# MPPT.net
KiCad netlist of a schematic drawn in Altium Designer
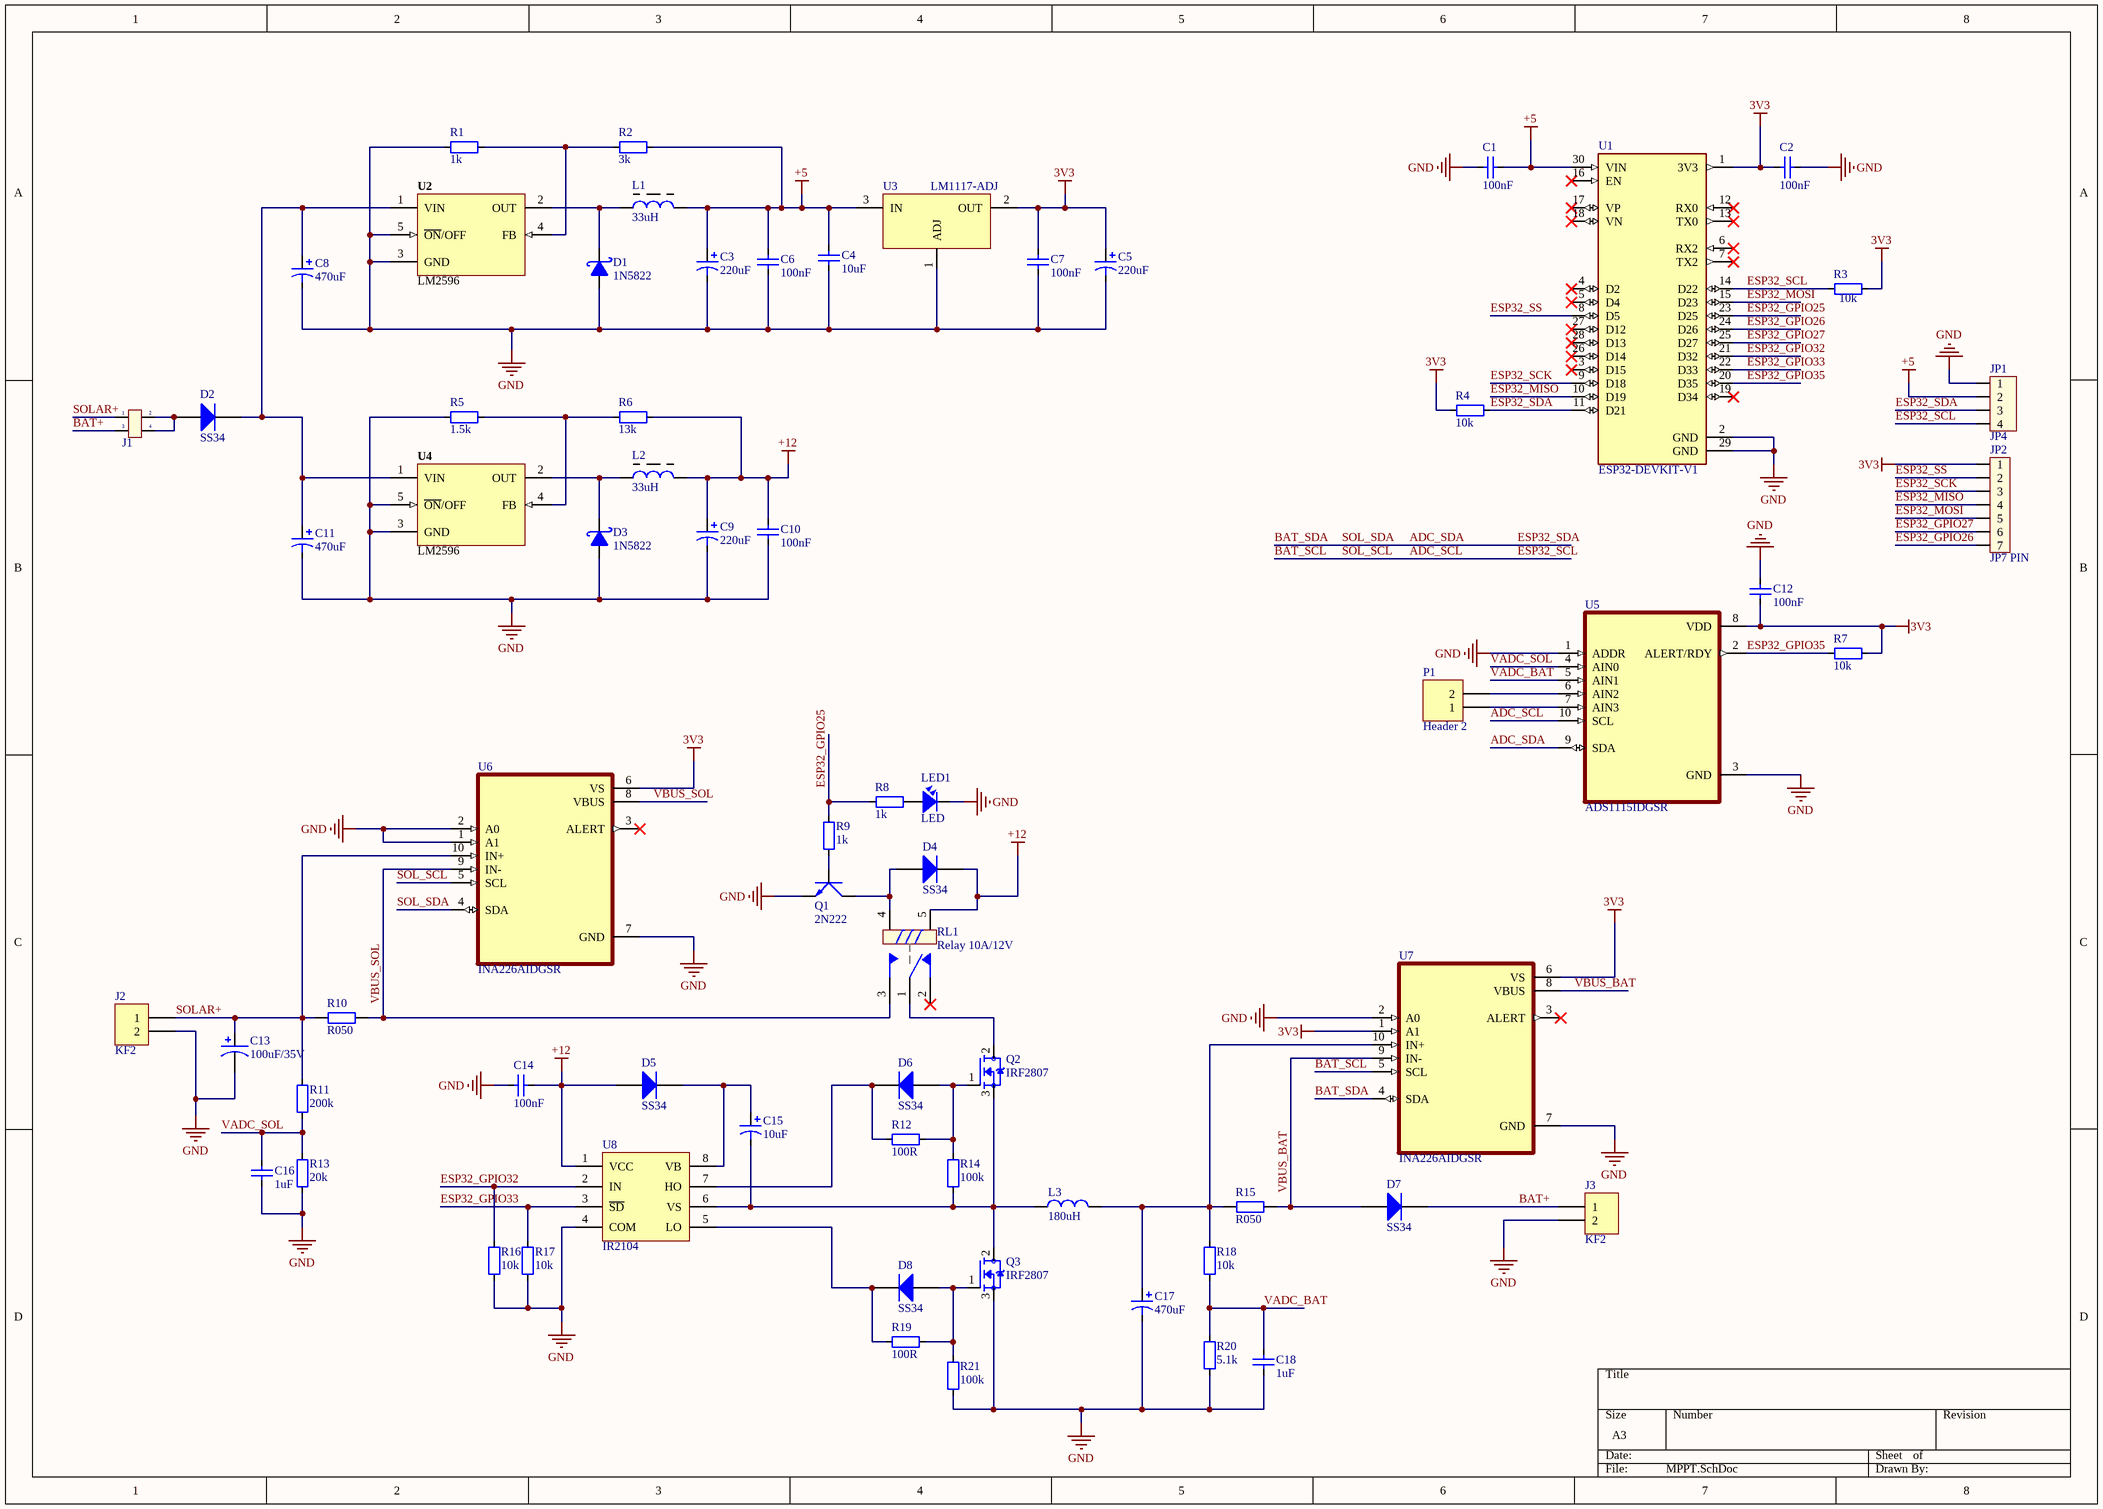
[diagram p0: MPPT.SchDoc]

(export (version "E")
  (design (tool "Eeschema 10.0.6"))
  (components
    (comp (ref "C1")
      (value "100nF")
      (footprint "CAP_0805")
      (description "Capacitor")
      (fields (field (name "PUBLISHER") "Altium Limited"))
      (libsource (lib "My Library") (part "CapSMD"))
    )
    (comp (ref "C2")
      (value "100nF")
      (footprint "CAP_0805")
      (description "Capacitor")
      (fields (field (name "PUBLISHER") "Altium Limited"))
      (libsource (lib "My Library") (part "CapSMD"))
    )
    (comp (ref "C3")
      (value "220uF")
      (footprint "C8mm")
      (description "220uF 25V 6x7mm")
      (fields (field (name "PUBLISHER") "Altium Limited"))
      (libsource (lib "My Library") (part "Cap Pol"))
    )
    (comp (ref "C4")
      (value "10uF")
      (footprint "CAP_0805")
      (description "Capacitor")
      (fields (field (name "PUBLISHER") "Altium Limited"))
      (libsource (lib "My Library") (part "CapSMD"))
    )
    (comp (ref "C5")
      (value "220uF")
      (footprint "C8mm")
      (description "220uF 25V 6x7mm")
      (fields (field (name "PUBLISHER") "Altium Limited"))
      (libsource (lib "My Library") (part "Cap Pol"))
    )
    (comp (ref "C6")
      (value "100nF")
      (footprint "CAP_0805")
      (description "Capacitor")
      (fields (field (name "PUBLISHER") "Altium Limited"))
      (libsource (lib "My Library") (part "CapSMD"))
    )
    (comp (ref "C7")
      (value "100nF")
      (footprint "CAP_0805")
      (description "Capacitor")
      (fields (field (name "PUBLISHER") "Altium Limited"))
      (libsource (lib "My Library") (part "CapSMD"))
    )
    (comp (ref "C8")
      (value "470uF")
      (footprint "C8mm")
      (description "220uF 50V 8x12mm")
      (fields (field (name "PUBLISHER") "Altium Limited"))
      (libsource (lib "My Library") (part "Cap Pol"))
    )
    (comp (ref "C9")
      (value "220uF")
      (footprint "C8mm")
      (description "220uF 25V 6x7mm")
      (fields (field (name "PUBLISHER") "Altium Limited"))
      (libsource (lib "My Library") (part "Cap Pol"))
    )
    (comp (ref "C10")
      (value "100nF")
      (footprint "CAP_0805")
      (description "Capacitor")
      (fields (field (name "PUBLISHER") "Altium Limited"))
      (libsource (lib "My Library") (part "CapSMD"))
    )
    (comp (ref "C11")
      (value "470uF")
      (footprint "C8mm")
      (description "220uF 50V 8x12mm")
      (fields (field (name "PUBLISHER") "Altium Limited"))
      (libsource (lib "My Library") (part "Cap Pol"))
    )
    (comp (ref "C12")
      (value "100nF")
      (footprint "CAP_0805")
      (description "Capacitor")
      (fields (field (name "PUBLISHER") "Altium Limited"))
      (libsource (lib "My Library") (part "CapSMD"))
    )
    (comp (ref "C13")
      (value "100uF/35V")
      (footprint "CA-ALU-6.3")
      (description "Polarized Capacitor (Axial)")
      (fields (field (name "PUBLISHER") "Altium Limited"))
      (libsource (lib "") (part "Cap Pol_1"))
    )
    (comp (ref "C14")
      (value "100nF")
      (footprint "CAP_0805")
      (description "Capacitor")
      (fields (field (name "PUBLISHER") "Altium Limited"))
      (libsource (lib "My Library") (part "CapSMD"))
    )
    (comp (ref "C15")
      (value "10uF")
      (footprint "CAP_35TQC10MYF")
      (description "220uF 25V 6x7mm")
      (fields (field (name "PUBLISHER") "Altium Limited"))
      (libsource (lib "My Library") (part "Cap Pol"))
    )
    (comp (ref "C16")
      (value "1uF")
      (footprint "CAP_0805")
      (description "Capacitor")
      (fields (field (name "PUBLISHER") "Altium Limited"))
      (libsource (lib "My Library") (part "CapSMD"))
    )
    (comp (ref "C17")
      (value "470uF")
      (footprint "C8mm")
      (description "470uF 50V 8x12mm")
      (fields (field (name "PUBLISHER") "Altium Limited"))
      (libsource (lib "My Library") (part "Cap Pol"))
    )
    (comp (ref "C18")
      (value "1uF")
      (footprint "CAP_0805")
      (description "Capacitor")
      (fields (field (name "PUBLISHER") "Altium Limited"))
      (libsource (lib "My Library") (part "CapSMD"))
    )
    (comp (ref "D1")
      (value "1N5822")
      (footprint "SMA")
      (description "Schottky Rectifiers")
      (libsource (lib "My Library") (part "1N5822"))
    )
    (comp (ref "D2")
      (value "SS34")
      (footprint "SMA")
      (description "Dán")
      (libsource (lib "Altium_Lib_by_KhueNguyenCreator") (part "Diode SS34 ( 1N5822 )"))
    )
    (comp (ref "D3")
      (value "1N5822")
      (footprint "SMA")
      (description "Schottky Rectifiers")
      (libsource (lib "My Library") (part "1N5822"))
    )
    (comp (ref "D4")
      (value "SS34")
      (footprint "SMA")
      (libsource (lib "Altium_Lib_by_KhueNguyenCreator") (part "Diode SS34 ( 1N5822 )"))
    )
    (comp (ref "D5")
      (value "SS34")
      (footprint "SMA")
      (libsource (lib "Altium_Lib_by_KhueNguyenCreator") (part "Diode SS34 ( 1N5822 )"))
    )
    (comp (ref "D6")
      (value "SS34")
      (footprint "SMA")
      (description "Dán")
      (libsource (lib "Altium_Lib_by_KhueNguyenCreator") (part "Diode SS34 ( 1N5822 )"))
    )
    (comp (ref "D7")
      (value "SS34")
      (footprint "SMA")
      (description "Dán")
      (libsource (lib "Altium_Lib_by_KhueNguyenCreator") (part "Diode SS34 ( 1N5822 )"))
    )
    (comp (ref "D8")
      (value "SS34")
      (footprint "SMA")
      (description "Dán")
      (libsource (lib "Altium_Lib_by_KhueNguyenCreator") (part "Diode SS34 ( 1N5822 )"))
    )
    (comp (ref "J1") (value "Jumper 2x2") (footprint "HDR2X2") (libsource (lib "My Library") (part "JP2x2")))
    (comp (ref "J2")
      (value "KF2")
      (footprint "KF2-5.08T")
      (fields
        (field (name "MANUFACTURER") "Würth Elektronik eiSos GmbH")
        (field (name "PARTNO") "691103110002")
        (field (name "CREATED BY") "Karrer Zheng")
      )
      (libsource (lib "") (part "KF2_1"))
    )
    (comp (ref "J3")
      (value "KF2")
      (footprint "KF2-5.08T")
      (fields
        (field (name "MANUFACTURER") "Würth Elektronik eiSos GmbH")
        (field (name "PARTNO") "691103110002")
        (field (name "CREATED BY") "Karrer Zheng")
      )
      (libsource (lib "My Library") (part "KF2"))
    )
    (comp (ref "JP1")
      (value "JP4")
      (footprint "CON4")
      (description "Connector 4")
      (libsource (lib "My Library") (part "Con4"))
    )
    (comp (ref "JP2") (value "JP7 PIN") (footprint "JP7") (libsource (lib "My Library") (part "JP7")))
    (comp (ref "L1")
      (value "33uH")
      (footprint "L-SMD-M-7.3x4.5")
      (description "33uH CD127 3A 12x12x7mm")
      (libsource (lib "My Library") (part "Inductor Ferit"))
    )
    (comp (ref "L2")
      (value "33uH")
      (footprint "L-SMD-M-7.3x4.5")
      (description "33uH CD127 3A 12x12x7mm")
      (libsource (lib "My Library") (part "Inductor Ferit"))
    )
    (comp (ref "L3")
      (value "180uH")
      (footprint "L-DIP-M-13.5x6")
      (description "180uH 4A 13mm")
      (libsource (lib "My Library") (part "Inductor"))
    )
    (comp (ref "LED1")
      (value "LED")
      (footprint "LED-0805-Red")
      (description "LED Single colour Green and Red")
      (libsource (lib "My Library") (part "LED"))
    )
    (comp (ref "P1")
      (value "Header 2")
      (footprint "HDR1X2")
      (description "Header, 2-Pin")
      (fields (field (name "PUBLISHER") "Altium Limited"))
      (libsource (lib "My Library") (part "Header 2"))
    )
    (comp (ref "Q1")
      (value "2N222")
      (footprint "SOT23")
      (description "NPN 600mW, ECB")
      (libsource (lib "My Library") (part "2N222"))
    )
    (comp (ref "Q2") (value "IRF2807") (footprint "TO-220") (libsource (lib "My Library") (part "IRF2807")))
    (comp (ref "Q3") (value "IRF2807") (footprint "TO-220") (libsource (lib "My Library") (part "IRF2807")))
    (comp (ref "R1")
      (value "1k")
      (footprint "RES-SMD-0805")
      (description "Resistor")
      (fields
        (field (name "MANUFACTURER") "Generic Components")
        (field (name "PUBLISHER") "Altium Hobart Technology Centre")
      )
      (libsource (lib "My Library") (part "Resistor - SMD"))
    )
    (comp (ref "R2")
      (value "3k")
      (footprint "RES-SMD-0805")
      (description "Resistor")
      (fields
        (field (name "MANUFACTURER") "Generic Components")
        (field (name "PUBLISHER") "Altium Hobart Technology Centre")
      )
      (libsource (lib "My Library") (part "Resistor - SMD"))
    )
    (comp (ref "R3")
      (value "10k")
      (footprint "RES-SMD-0805")
      (description "Resistor")
      (fields
        (field (name "MANUFACTURER") "Generic Components")
        (field (name "PUBLISHER") "Altium Hobart Technology Centre")
      )
      (libsource (lib "My Library") (part "Resistor - SMD"))
    )
    (comp (ref "R4")
      (value "10k")
      (footprint "RES-SMD-0805")
      (description "Resistor")
      (fields
        (field (name "MANUFACTURER") "Generic Components")
        (field (name "PUBLISHER") "Altium Hobart Technology Centre")
      )
      (libsource (lib "My Library") (part "Resistor - SMD"))
    )
    (comp (ref "R5")
      (value "1.5k")
      (footprint "RES-SMD-0805")
      (description "Resistor")
      (fields
        (field (name "MANUFACTURER") "Generic Components")
        (field (name "PUBLISHER") "Altium Hobart Technology Centre")
      )
      (libsource (lib "My Library") (part "Resistor - SMD"))
    )
    (comp (ref "R6")
      (value "13k")
      (footprint "RES-SMD-0805")
      (description "Resistor")
      (fields
        (field (name "MANUFACTURER") "Generic Components")
        (field (name "PUBLISHER") "Altium Hobart Technology Centre")
      )
      (libsource (lib "My Library") (part "Resistor - SMD"))
    )
    (comp (ref "R7")
      (value "10k")
      (footprint "RES-SMD-0805")
      (description "Resistor")
      (fields
        (field (name "MANUFACTURER") "Generic Components")
        (field (name "PUBLISHER") "Altium Hobart Technology Centre")
      )
      (libsource (lib "My Library") (part "Resistor - SMD"))
    )
    (comp (ref "R8")
      (value "1k")
      (footprint "RES-SMD-0805")
      (description "Resistor")
      (fields
        (field (name "MANUFACTURER") "Generic Components")
        (field (name "PUBLISHER") "Altium Hobart Technology Centre")
      )
      (libsource (lib "My Library") (part "Resistor - SMD"))
    )
    (comp (ref "R9")
      (value "1k")
      (footprint "RES-SMD-0805")
      (description "Resistor")
      (fields
        (field (name "MANUFACTURER") "Generic Components")
        (field (name "PUBLISHER") "Altium Hobart Technology Centre")
      )
      (libsource (lib "My Library") (part "Resistor - SMD"))
    )
    (comp (ref "R10")
      (value "R050")
      (footprint "RES-SMD-2512")
      (description "Resistor SMD")
      (fields
        (field (name "MANUFACTURER") "Generic Components")
        (field (name "PUBLISHER") "Altium Hobart Technology Centre")
      )
      (libsource (lib "") (part "Resistor - SMD_1"))
    )
    (comp (ref "R11")
      (value "200k")
      (footprint "RES-SMD-0805")
      (description "Resistor")
      (fields
        (field (name "MANUFACTURER") "Generic Components")
        (field (name "PUBLISHER") "Altium Hobart Technology Centre")
      )
      (libsource (lib "My Library") (part "Resistor - SMD"))
    )
    (comp (ref "R12")
      (value "100R")
      (footprint "RES-SMD-0805")
      (description "Resistor")
      (fields
        (field (name "MANUFACTURER") "Generic Components")
        (field (name "PUBLISHER") "Altium Hobart Technology Centre")
      )
      (libsource (lib "My Library") (part "Resistor - SMD"))
    )
    (comp (ref "R13")
      (value "20k")
      (footprint "RES-SMD-0805")
      (description "Resistor")
      (fields
        (field (name "MANUFACTURER") "Generic Components")
        (field (name "PUBLISHER") "Altium Hobart Technology Centre")
      )
      (libsource (lib "My Library") (part "Resistor - SMD"))
    )
    (comp (ref "R14")
      (value "100k")
      (footprint "RES-SMD-0805")
      (description "Resistor")
      (fields
        (field (name "MANUFACTURER") "Generic Components")
        (field (name "PUBLISHER") "Altium Hobart Technology Centre")
      )
      (libsource (lib "My Library") (part "Resistor - SMD"))
    )
    (comp (ref "R15")
      (value "R050")
      (footprint "RES-SMD-2512")
      (description "Resistor SMD")
      (fields
        (field (name "MANUFACTURER") "Generic Components")
        (field (name "PUBLISHER") "Altium Hobart Technology Centre")
      )
      (libsource (lib "") (part "Resistor - SMD_1"))
    )
    (comp (ref "R16")
      (value "10k")
      (footprint "RES-SMD-0805")
      (description "Resistor")
      (fields
        (field (name "MANUFACTURER") "Generic Components")
        (field (name "PUBLISHER") "Altium Hobart Technology Centre")
      )
      (libsource (lib "My Library") (part "Resistor - SMD"))
    )
    (comp (ref "R17")
      (value "10k")
      (footprint "RES-SMD-0805")
      (description "Resistor")
      (fields
        (field (name "MANUFACTURER") "Generic Components")
        (field (name "PUBLISHER") "Altium Hobart Technology Centre")
      )
      (libsource (lib "My Library") (part "Resistor - SMD"))
    )
    (comp (ref "R18")
      (value "10k")
      (footprint "RES-SMD-0805")
      (description "Resistor")
      (fields
        (field (name "MANUFACTURER") "Generic Components")
        (field (name "PUBLISHER") "Altium Hobart Technology Centre")
      )
      (libsource (lib "My Library") (part "Resistor - SMD"))
    )
    (comp (ref "R19")
      (value "100R")
      (footprint "RES-SMD-0805")
      (description "Resistor")
      (fields
        (field (name "MANUFACTURER") "Generic Components")
        (field (name "PUBLISHER") "Altium Hobart Technology Centre")
      )
      (libsource (lib "My Library") (part "Resistor - SMD"))
    )
    (comp (ref "R20")
      (value "5.1k")
      (footprint "RES-SMD-0805")
      (description "Resistor")
      (fields
        (field (name "MANUFACTURER") "Generic Components")
        (field (name "PUBLISHER") "Altium Hobart Technology Centre")
      )
      (libsource (lib "My Library") (part "Resistor - SMD"))
    )
    (comp (ref "R21")
      (value "100k")
      (footprint "RES-SMD-0805")
      (description "Resistor")
      (fields
        (field (name "MANUFACTURER") "Generic Components")
        (field (name "PUBLISHER") "Altium Hobart Technology Centre")
      )
      (libsource (lib "My Library") (part "Resistor - SMD"))
    )
    (comp (ref "RL1")
      (value "Relay 10A/12V")
      (footprint "RELAY5PIN-10A")
      (description "Relay SPDT,10A - 12VDC 5 Pin")
      (libsource (lib "My Library") (part "Relay 5"))
    )
    (comp (ref "U1")
      (value "ESP32-DEVKIT-V1")
      (footprint "MODULE_ESP32_DEVKIT_V1")
      (libsource (lib "ESP32-DEVKIT-V1") (part "ESP32-DEVKIT-V1"))
    )
    (comp (ref "U2") (value "LM2596") (footprint "TO-263") (libsource (lib "My Library") (part "LM2596")))
    (comp (ref "U3")
      (value "LM1117-ADJ")
      (footprint "LM1117-SOP")
      (description "800mA Low-Dropout Linear Regulator")
      (fields (field (name "CREATOR") "Nguyen Ba Bien"))
      (libsource (lib "My Library") (part "LM1117-ADJ"))
    )
    (comp (ref "U4") (value "LM2596") (footprint "TO-263") (libsource (lib "My Library") (part "LM2596")))
    (comp (ref "U5")
      (value "ADS1115IDGSR")
      (footprint "SOP50P490X110-10N")
      (libsource (lib "ADS1115IDGSR") (part "ADS1115IDGSR"))
    )
    (comp (ref "U6")
      (value "INA226AIDGSR")
      (footprint "SOP50P490X110-10N")
      (description "36V, 16-bit, ultra-precise i2c output current/voltage/power monitor w/alert 10-VSSOP -40 to 125")
      (fields
        (field (name "MF") "Texas Instruments")
        (field (name "BUYPART") "https://www.snapeda.com/parts/INA226AIDGSR/Texas%20Instruments/view-part/53552/?ref=eda")
      )
      (libsource (lib "INA226AIDGSR") (part "INA226AIDGSR"))
    )
    (comp (ref "U7")
      (value "INA226AIDGSR")
      (footprint "SOP50P490X110-10N")
      (description "36V, 16-bit, ultra-precise i2c output current/voltage/power monitor w/alert 10-VSSOP -40 to 125")
      (fields
        (field (name "MF") "Texas Instruments")
        (field (name "BUYPART") "https://www.snapeda.com/parts/INA226AIDGSR/Texas%20Instruments/view-part/53552/?ref=eda")
      )
      (libsource (lib "INA226AIDGSR") (part "INA226AIDGSR"))
    )
    (comp (ref "U8")
      (value "IR2104")
      (footprint "SO-8N")
      (description "Half-Bridge Driver")
      (libsource (lib "My Library") (part "IR2184"))
    )
  )
  (nets
    (net (code "1") (name "+5") (class "Default")
      (node (ref "C1") (pin "2") (pinfunction "2_2") (pintype "passive"))
      (node (ref "C3") (pin "1") (pinfunction "1_1") (pintype "passive"))
      (node (ref "C4") (pin "1") (pinfunction "1_1") (pintype "passive"))
      (node (ref "C6") (pin "1") (pinfunction "1_1") (pintype "passive"))
      (node (ref "JP1") (pin "2") (pinfunction "2_2") (pintype "passive"))
      (node (ref "L1") (pin "2") (pinfunction "2_2") (pintype "passive"))
      (node (ref "R2") (pin "2") (pinfunction "2_2") (pintype "passive"))
      (node (ref "U1") (pin "30") (pinfunction "VIN_30") (pintype "input"))
      (node (ref "U3") (pin "3") (pinfunction "IN_3") (pintype "passive"))
    )
    (net (code "2") (name "+12") (class "Default")
      (node (ref "C10") (pin "1") (pinfunction "1_1") (pintype "passive"))
      (node (ref "C14") (pin "1") (pinfunction "1_1") (pintype "passive"))
      (node (ref "C9") (pin "1") (pinfunction "1_1") (pintype "passive"))
      (node (ref "D4") (pin "2") (pinfunction "K_2") (pintype "passive"))
      (node (ref "D5") (pin "1") (pinfunction "A_1") (pintype "passive"))
      (node (ref "L2") (pin "2") (pinfunction "2_2") (pintype "passive"))
      (node (ref "R6") (pin "2") (pinfunction "2_2") (pintype "passive"))
      (node (ref "RL1") (pin "5") (pinfunction "5_5") (pintype "passive"))
      (node (ref "U8") (pin "1") (pinfunction "VCC_1") (pintype "passive"))
    )
    (net (code "3") (name "/ADC_SCL") (class "Default")
      (node (ref "JP1") (pin "4") (pinfunction "4_4") (pintype "passive"))
      (node (ref "R3") (pin "2") (pinfunction "2_2") (pintype "passive"))
      (node (ref "U1") (pin "14") (pinfunction "D22_14") (pintype "bidirectional"))
      (node (ref "U5") (pin "10") (pinfunction "SCL_10") (pintype "input"))
      (node (ref "U6") (pin "5") (pinfunction "SCL_5") (pintype "input"))
      (node (ref "U7") (pin "5") (pinfunction "SCL_5") (pintype "input"))
    )
    (net (code "4") (name "/ADC_SDA") (class "Default")
      (node (ref "JP1") (pin "3") (pinfunction "3_3") (pintype "passive"))
      (node (ref "R4") (pin "2") (pinfunction "2_2") (pintype "passive"))
      (node (ref "U1") (pin "11") (pinfunction "D21_11") (pintype "bidirectional"))
      (node (ref "U5") (pin "9") (pinfunction "SDA_9") (pintype "bidirectional"))
      (node (ref "U6") (pin "4") (pinfunction "SDA_4") (pintype "bidirectional"))
      (node (ref "U7") (pin "4") (pinfunction "SDA_4") (pintype "bidirectional"))
    )
    (net (code "5") (name "/BAT+") (class "Default")
      (node (ref "D7") (pin "2") (pinfunction "K_2") (pintype "passive"))
      (node (ref "J1") (pin "3") (pinfunction "3_3") (pintype "passive"))
      (node (ref "J3") (pin "1") (pinfunction "1_1") (pintype "passive"))
    )
    (net (code "6") (name "/ESP32_GPIO25") (class "Default")
      (node (ref "R8") (pin "2") (pinfunction "2_2") (pintype "passive"))
      (node (ref "R9") (pin "2") (pinfunction "2_2") (pintype "passive"))
      (node (ref "U1") (pin "23") (pinfunction "D25_23") (pintype "bidirectional"))
    )
    (net (code "7") (name "/ESP32_GPIO26") (class "Default")
      (node (ref "JP2") (pin "7") (pinfunction "7_7") (pintype "passive"))
      (node (ref "U1") (pin "24") (pinfunction "D26_24") (pintype "bidirectional"))
    )
    (net (code "8") (name "/ESP32_GPIO27") (class "Default")
      (node (ref "JP2") (pin "6") (pinfunction "6_6") (pintype "passive"))
      (node (ref "U1") (pin "25") (pinfunction "D27_25") (pintype "bidirectional"))
    )
    (net (code "9") (name "/ESP32_GPIO32") (class "Default")
      (node (ref "R16") (pin "2") (pinfunction "2_2") (pintype "passive"))
      (node (ref "U1") (pin "21") (pinfunction "D32_21") (pintype "bidirectional"))
      (node (ref "U8") (pin "2") (pinfunction "IN_2") (pintype "passive"))
    )
    (net (code "10") (name "/ESP32_GPIO33") (class "Default")
      (node (ref "R17") (pin "2") (pinfunction "2_2") (pintype "passive"))
      (node (ref "U1") (pin "22") (pinfunction "D33_22") (pintype "bidirectional"))
      (node (ref "U8") (pin "3") (pinfunction "~{SD}_3") (pintype "passive"))
    )
    (net (code "11") (name "/ESP32_GPIO35") (class "Default")
      (node (ref "R7") (pin "2") (pinfunction "2_2") (pintype "passive"))
      (node (ref "U1") (pin "20") (pinfunction "D35_20") (pintype "bidirectional"))
      (node (ref "U5") (pin "2") (pinfunction "ALERT/RDY_2") (pintype "output"))
    )
    (net (code "12") (name "/ESP32_MISO") (class "Default")
      (node (ref "JP2") (pin "4") (pinfunction "4_4") (pintype "passive"))
      (node (ref "U1") (pin "10") (pinfunction "D19_10") (pintype "bidirectional"))
    )
    (net (code "13") (name "/ESP32_MOSI") (class "Default")
      (node (ref "JP2") (pin "5") (pinfunction "5_5") (pintype "passive"))
      (node (ref "U1") (pin "15") (pinfunction "D23_15") (pintype "bidirectional"))
    )
    (net (code "14") (name "/ESP32_SCK") (class "Default")
      (node (ref "JP2") (pin "3") (pinfunction "3_3") (pintype "passive"))
      (node (ref "U1") (pin "9") (pinfunction "D18_9") (pintype "bidirectional"))
    )
    (net (code "15") (name "/ESP32_SS") (class "Default")
      (node (ref "JP2") (pin "2") (pinfunction "2_2") (pintype "passive"))
      (node (ref "U1") (pin "8") (pinfunction "D5_8") (pintype "bidirectional"))
    )
    (net (code "16") (name "/SOLAR+") (class "Default")
      (node (ref "C13") (pin "1") (pinfunction "1_1") (pintype "passive"))
      (node (ref "J1") (pin "1") (pinfunction "1_1") (pintype "passive"))
      (node (ref "J2") (pin "1") (pinfunction "1_1") (pintype "passive"))
      (node (ref "R10") (pin "2") (pinfunction "2_2") (pintype "passive"))
      (node (ref "R11") (pin "2") (pinfunction "2_2") (pintype "passive"))
      (node (ref "U6") (pin "10") (pinfunction "IN+_10") (pintype "input"))
    )
    (net (code "17") (name "/VADC_BAT") (class "Default")
      (node (ref "C18") (pin "1") (pinfunction "1_1") (pintype "passive"))
      (node (ref "R18") (pin "2") (pinfunction "2_2") (pintype "passive"))
      (node (ref "R20") (pin "1") (pinfunction "1_1") (pintype "passive"))
      (node (ref "U5") (pin "5") (pinfunction "AIN1_5") (pintype "input"))
    )
    (net (code "18") (name "/VADC_SOL") (class "Default")
      (node (ref "C16") (pin "1") (pinfunction "1_1") (pintype "passive"))
      (node (ref "R11") (pin "1") (pinfunction "1_1") (pintype "passive"))
      (node (ref "R13") (pin "1") (pinfunction "1_1") (pintype "passive"))
      (node (ref "U5") (pin "4") (pinfunction "AIN0_4") (pintype "input"))
    )
    (net (code "19") (name "/VBUS_BAT") (class "Default")
      (node (ref "D7") (pin "1") (pinfunction "A_1") (pintype "passive"))
      (node (ref "R15") (pin "1") (pinfunction "1_1") (pintype "passive"))
      (node (ref "U7") (pin "8") (pinfunction "VBUS_8") (pintype "power_in"))
      (node (ref "U7") (pin "9") (pinfunction "IN-_9") (pintype "input"))
    )
    (net (code "20") (name "/VBUS_SOL") (class "Default")
      (node (ref "R10") (pin "1") (pinfunction "1_1") (pintype "passive"))
      (node (ref "RL1") (pin "3") (pinfunction "3_3") (pintype "passive"))
      (node (ref "U6") (pin "8") (pinfunction "VBUS_8") (pintype "power_in"))
      (node (ref "U6") (pin "9") (pinfunction "IN-_9") (pintype "input"))
    )
    (net (code "21") (name "3V3") (class "Default")
      (node (ref "C12") (pin "2") (pinfunction "2_2") (pintype "passive"))
      (node (ref "C2") (pin "1") (pinfunction "1_1") (pintype "passive"))
      (node (ref "C5") (pin "1") (pinfunction "1_1") (pintype "passive"))
      (node (ref "C7") (pin "1") (pinfunction "1_1") (pintype "passive"))
      (node (ref "JP2") (pin "1") (pinfunction "1_1") (pintype "passive"))
      (node (ref "R3") (pin "1") (pinfunction "1_1") (pintype "passive"))
      (node (ref "R4") (pin "1") (pinfunction "1_1") (pintype "passive"))
      (node (ref "R7") (pin "1") (pinfunction "1_1") (pintype "passive"))
      (node (ref "U1") (pin "1") (pinfunction "3V3_1") (pintype "output"))
      (node (ref "U3") (pin "2") (pinfunction "OUT_2") (pintype "passive"))
      (node (ref "U5") (pin "8") (pinfunction "VDD_8") (pintype "power_in"))
      (node (ref "U6") (pin "6") (pinfunction "VS_6") (pintype "power_in"))
      (node (ref "U7") (pin "1") (pinfunction "A1_1") (pintype "input"))
      (node (ref "U7") (pin "6") (pinfunction "VS_6") (pintype "power_in"))
    )
    (net (code "22") (name "GND") (class "Default")
      (node (ref "C1") (pin "1") (pinfunction "1_1") (pintype "passive"))
      (node (ref "C10") (pin "2") (pinfunction "2_2") (pintype "passive"))
      (node (ref "C11") (pin "2") (pinfunction "2_2") (pintype "passive"))
      (node (ref "C12") (pin "1") (pinfunction "1_1") (pintype "passive"))
      (node (ref "C13") (pin "2") (pinfunction "2_2") (pintype "passive"))
      (node (ref "C14") (pin "2") (pinfunction "2_2") (pintype "passive"))
      (node (ref "C16") (pin "2") (pinfunction "2_2") (pintype "passive"))
      (node (ref "C17") (pin "2") (pinfunction "2_2") (pintype "passive"))
      (node (ref "C18") (pin "2") (pinfunction "2_2") (pintype "passive"))
      (node (ref "C2") (pin "2") (pinfunction "2_2") (pintype "passive"))
      (node (ref "C3") (pin "2") (pinfunction "2_2") (pintype "passive"))
      (node (ref "C4") (pin "2") (pinfunction "2_2") (pintype "passive"))
      (node (ref "C5") (pin "2") (pinfunction "2_2") (pintype "passive"))
      (node (ref "C6") (pin "2") (pinfunction "2_2") (pintype "passive"))
      (node (ref "C7") (pin "2") (pinfunction "2_2") (pintype "passive"))
      (node (ref "C8") (pin "2") (pinfunction "2_2") (pintype "passive"))
      (node (ref "C9") (pin "2") (pinfunction "2_2") (pintype "passive"))
      (node (ref "D1") (pin "1") (pinfunction "A_1") (pintype "passive"))
      (node (ref "D3") (pin "1") (pinfunction "A_1") (pintype "passive"))
      (node (ref "J2") (pin "2") (pinfunction "2_2") (pintype "passive"))
      (node (ref "J3") (pin "2") (pinfunction "2_2") (pintype "passive"))
      (node (ref "JP1") (pin "1") (pinfunction "1_1") (pintype "passive"))
      (node (ref "LED1") (pin "2") (pinfunction "2_2") (pintype "passive"))
      (node (ref "Q1") (pin "1") (pinfunction "E_1") (pintype "passive"))
      (node (ref "Q3") (pin "3") (pinfunction "S_3") (pintype "passive"))
      (node (ref "R1") (pin "1") (pinfunction "1_1") (pintype "passive"))
      (node (ref "R13") (pin "2") (pinfunction "2_2") (pintype "passive"))
      (node (ref "R16") (pin "1") (pinfunction "1_1") (pintype "passive"))
      (node (ref "R17") (pin "1") (pinfunction "1_1") (pintype "passive"))
      (node (ref "R20") (pin "2") (pinfunction "2_2") (pintype "passive"))
      (node (ref "R21") (pin "2") (pinfunction "2_2") (pintype "passive"))
      (node (ref "R5") (pin "1") (pinfunction "1_1") (pintype "passive"))
      (node (ref "U1") (pin "2") (pinfunction "GND_2") (pintype "power_in"))
      (node (ref "U1") (pin "29") (pinfunction "GND_29") (pintype "power_in"))
      (node (ref "U2") (pin "3") (pinfunction "GND_3") (pintype "power_in"))
      (node (ref "U2") (pin "5") (pinfunction "~{ON}/OFF_5") (pintype "input"))
      (node (ref "U3") (pin "1") (pinfunction "ADJ_1") (pintype "passive"))
      (node (ref "U4") (pin "3") (pinfunction "GND_3") (pintype "power_in"))
      (node (ref "U4") (pin "5") (pinfunction "~{ON}/OFF_5") (pintype "input"))
      (node (ref "U5") (pin "1") (pinfunction "ADDR_1") (pintype "input"))
      (node (ref "U5") (pin "3") (pinfunction "GND_3") (pintype "power_in"))
      (node (ref "U6") (pin "1") (pinfunction "A1_1") (pintype "input"))
      (node (ref "U6") (pin "2") (pinfunction "A0_2") (pintype "input"))
      (node (ref "U6") (pin "7") (pinfunction "GND_7") (pintype "power_in"))
      (node (ref "U7") (pin "2") (pinfunction "A0_2") (pintype "input"))
      (node (ref "U7") (pin "7") (pinfunction "GND_7") (pintype "power_in"))
      (node (ref "U8") (pin "4") (pinfunction "COM_4") (pintype "passive"))
    )
    (net (code "23") (name "Net-(D1-K)") (class "Default")
      (node (ref "D1") (pin "2") (pinfunction "K_2") (pintype "passive"))
      (node (ref "L1") (pin "1") (pinfunction "1_1") (pintype "passive"))
      (node (ref "U2") (pin "2") (pinfunction "OUT_2") (pintype "power_in"))
    )
    (net (code "24") (name "Net-(D2-A)") (class "Default")
      (node (ref "D2") (pin "1") (pinfunction "A_1") (pintype "passive"))
      (node (ref "J1") (pin "2") (pinfunction "2_2") (pintype "passive"))
      (node (ref "J1") (pin "4") (pinfunction "4_4") (pintype "passive"))
    )
    (net (code "25") (name "Net-(D2-K)") (class "Default")
      (node (ref "C11") (pin "1") (pinfunction "1_1") (pintype "passive"))
      (node (ref "C8") (pin "1") (pinfunction "1_1") (pintype "passive"))
      (node (ref "D2") (pin "2") (pinfunction "K_2") (pintype "passive"))
      (node (ref "U2") (pin "1") (pinfunction "VIN_1") (pintype "power_in"))
      (node (ref "U4") (pin "1") (pinfunction "VIN_1") (pintype "power_in"))
    )
    (net (code "26") (name "Net-(D3-K)") (class "Default")
      (node (ref "D3") (pin "2") (pinfunction "K_2") (pintype "passive"))
      (node (ref "L2") (pin "1") (pinfunction "1_1") (pintype "passive"))
      (node (ref "U4") (pin "2") (pinfunction "OUT_2") (pintype "power_in"))
    )
    (net (code "27") (name "Net-(D4-A)") (class "Default")
      (node (ref "D4") (pin "1") (pinfunction "A_1") (pintype "passive"))
      (node (ref "Q1") (pin "3") (pinfunction "C_3") (pintype "passive"))
      (node (ref "RL1") (pin "4") (pinfunction "4_4") (pintype "passive"))
    )
    (net (code "28") (name "Net-(D5-K)") (class "Default")
      (node (ref "C15") (pin "1") (pinfunction "1_1") (pintype "passive"))
      (node (ref "D5") (pin "2") (pinfunction "K_2") (pintype "passive"))
      (node (ref "U8") (pin "8") (pinfunction "VB_8") (pintype "passive"))
    )
    (net (code "29") (name "Net-(D6-A)") (class "Default")
      (node (ref "D6") (pin "1") (pinfunction "A_1") (pintype "passive"))
      (node (ref "Q2") (pin "1") (pinfunction "G_1") (pintype "passive"))
      (node (ref "R12") (pin "1") (pinfunction "1_1") (pintype "passive"))
      (node (ref "R14") (pin "1") (pinfunction "1_1") (pintype "passive"))
    )
    (net (code "30") (name "Net-(D6-K)") (class "Default")
      (node (ref "D6") (pin "2") (pinfunction "K_2") (pintype "passive"))
      (node (ref "R12") (pin "2") (pinfunction "2_2") (pintype "passive"))
      (node (ref "U8") (pin "7") (pinfunction "HO_7") (pintype "passive"))
    )
    (net (code "31") (name "Net-(D8-A)") (class "Default")
      (node (ref "D8") (pin "1") (pinfunction "A_1") (pintype "passive"))
      (node (ref "Q3") (pin "1") (pinfunction "G_1") (pintype "passive"))
      (node (ref "R19") (pin "1") (pinfunction "1_1") (pintype "passive"))
      (node (ref "R21") (pin "1") (pinfunction "1_1") (pintype "passive"))
    )
    (net (code "32") (name "Net-(D8-K)") (class "Default")
      (node (ref "D8") (pin "2") (pinfunction "K_2") (pintype "passive"))
      (node (ref "R19") (pin "2") (pinfunction "2_2") (pintype "passive"))
      (node (ref "U8") (pin "5") (pinfunction "LO_5") (pintype "passive"))
    )
    (net (code "33") (name "Net-(LED1-Pad1)") (class "Default")
      (node (ref "LED1") (pin "1") (pinfunction "1_1") (pintype "passive"))
      (node (ref "R8") (pin "1") (pinfunction "1_1") (pintype "passive"))
    )
    (net (code "34") (name "Net-(Q1-B)") (class "Default")
      (node (ref "Q1") (pin "2") (pinfunction "B_2") (pintype "passive"))
      (node (ref "R9") (pin "1") (pinfunction "1_1") (pintype "passive"))
    )
    (net (code "35") (name "Net-(Q2-D)") (class "Default")
      (node (ref "Q2") (pin "2") (pinfunction "D_2") (pintype "passive"))
      (node (ref "RL1") (pin "1") (pinfunction "1_1") (pintype "passive"))
    )
    (net (code "36") (name "Net-(Q2-S)") (class "Default")
      (node (ref "C15") (pin "2") (pinfunction "2_2") (pintype "passive"))
      (node (ref "L3") (pin "1") (pinfunction "1_1") (pintype "passive"))
      (node (ref "Q2") (pin "3") (pinfunction "S_3") (pintype "passive"))
      (node (ref "Q3") (pin "2") (pinfunction "D_2") (pintype "passive"))
      (node (ref "R14") (pin "2") (pinfunction "2_2") (pintype "passive"))
      (node (ref "U8") (pin "6") (pinfunction "VS_6") (pintype "passive"))
    )
    (net (code "37") (name "Net-(U2-FB)") (class "Default")
      (node (ref "R1") (pin "2") (pinfunction "2_2") (pintype "passive"))
      (node (ref "R2") (pin "1") (pinfunction "1_1") (pintype "passive"))
      (node (ref "U2") (pin "4") (pinfunction "FB_4") (pintype "input"))
    )
    (net (code "38") (name "Net-(U4-FB)") (class "Default")
      (node (ref "R5") (pin "2") (pinfunction "2_2") (pintype "passive"))
      (node (ref "R6") (pin "1") (pinfunction "1_1") (pintype "passive"))
      (node (ref "U4") (pin "4") (pinfunction "FB_4") (pintype "input"))
    )
    (net (code "39") (name "Net-(U5-AIN2)") (class "Default")
      (node (ref "P1") (pin "2") (pinfunction "2_2") (pintype "passive"))
      (node (ref "U5") (pin "6") (pinfunction "AIN2_6") (pintype "input"))
    )
    (net (code "40") (name "Net-(U5-AIN3)") (class "Default")
      (node (ref "P1") (pin "1") (pinfunction "1_1") (pintype "passive"))
      (node (ref "U5") (pin "7") (pinfunction "AIN3_7") (pintype "input"))
    )
    (net (code "41") (name "Net-(U7-IN+)") (class "Default")
      (node (ref "C17") (pin "1") (pinfunction "1_1") (pintype "passive"))
      (node (ref "L3") (pin "2") (pinfunction "2_2") (pintype "passive"))
      (node (ref "R15") (pin "2") (pinfunction "2_2") (pintype "passive"))
      (node (ref "R18") (pin "1") (pinfunction "1_1") (pintype "passive"))
      (node (ref "U7") (pin "10") (pinfunction "IN+_10") (pintype "input"))
    )
    (net (code "42") (name "unconnected-(RL1-Pad2)") (class "Default")
      (node (ref "RL1") (pin "2") (pinfunction "2_2") (pintype "passive+no_connect"))
    )
    (net (code "43") (name "unconnected-(U1-D2-Pad4)") (class "Default")
      (node (ref "U1") (pin "4") (pinfunction "D2_4") (pintype "bidirectional+no_connect"))
    )
    (net (code "44") (name "unconnected-(U1-D4-Pad5)") (class "Default")
      (node (ref "U1") (pin "5") (pinfunction "D4_5") (pintype "bidirectional+no_connect"))
    )
    (net (code "45") (name "unconnected-(U1-D12-Pad27)") (class "Default")
      (node (ref "U1") (pin "27") (pinfunction "D12_27") (pintype "bidirectional+no_connect"))
    )
    (net (code "46") (name "unconnected-(U1-D13-Pad28)") (class "Default")
      (node (ref "U1") (pin "28") (pinfunction "D13_28") (pintype "bidirectional+no_connect"))
    )
    (net (code "47") (name "unconnected-(U1-D14-Pad26)") (class "Default")
      (node (ref "U1") (pin "26") (pinfunction "D14_26") (pintype "bidirectional+no_connect"))
    )
    (net (code "48") (name "unconnected-(U1-D15-Pad3)") (class "Default")
      (node (ref "U1") (pin "3") (pinfunction "D15_3") (pintype "bidirectional+no_connect"))
    )
    (net (code "49") (name "unconnected-(U1-D34-Pad19)") (class "Default")
      (node (ref "U1") (pin "19") (pinfunction "D34_19") (pintype "bidirectional+no_connect"))
    )
    (net (code "50") (name "unconnected-(U1-EN-Pad16)") (class "Default")
      (node (ref "U1") (pin "16") (pinfunction "EN_16") (pintype "input+no_connect"))
    )
    (net (code "51") (name "unconnected-(U1-RX0-Pad12)") (class "Default")
      (node (ref "U1") (pin "12") (pinfunction "RX0_12") (pintype "input+no_connect"))
    )
    (net (code "52") (name "unconnected-(U1-RX2-Pad6)") (class "Default")
      (node (ref "U1") (pin "6") (pinfunction "RX2_6") (pintype "input+no_connect"))
    )
    (net (code "53") (name "unconnected-(U1-TX0-Pad13)") (class "Default")
      (node (ref "U1") (pin "13") (pinfunction "TX0_13") (pintype "output+no_connect"))
    )
    (net (code "54") (name "unconnected-(U1-TX2-Pad7)") (class "Default")
      (node (ref "U1") (pin "7") (pinfunction "TX2_7") (pintype "output+no_connect"))
    )
    (net (code "55") (name "unconnected-(U1-VN-Pad18)") (class "Default")
      (node (ref "U1") (pin "18") (pinfunction "VN_18") (pintype "bidirectional+no_connect"))
    )
    (net (code "56") (name "unconnected-(U1-VP-Pad17)") (class "Default")
      (node (ref "U1") (pin "17") (pinfunction "VP_17") (pintype "bidirectional+no_connect"))
    )
    (net (code "57") (name "unconnected-(U6-ALERT-Pad3)") (class "Default")
      (node (ref "U6") (pin "3") (pinfunction "ALERT_3") (pintype "output+no_connect"))
    )
    (net (code "58") (name "unconnected-(U7-ALERT-Pad3)") (class "Default")
      (node (ref "U7") (pin "3") (pinfunction "ALERT_3") (pintype "output+no_connect"))
    )
  )
)
